# JTAG_CONFIG.net
KiCad netlist of a schematic drawn in Altium Designer
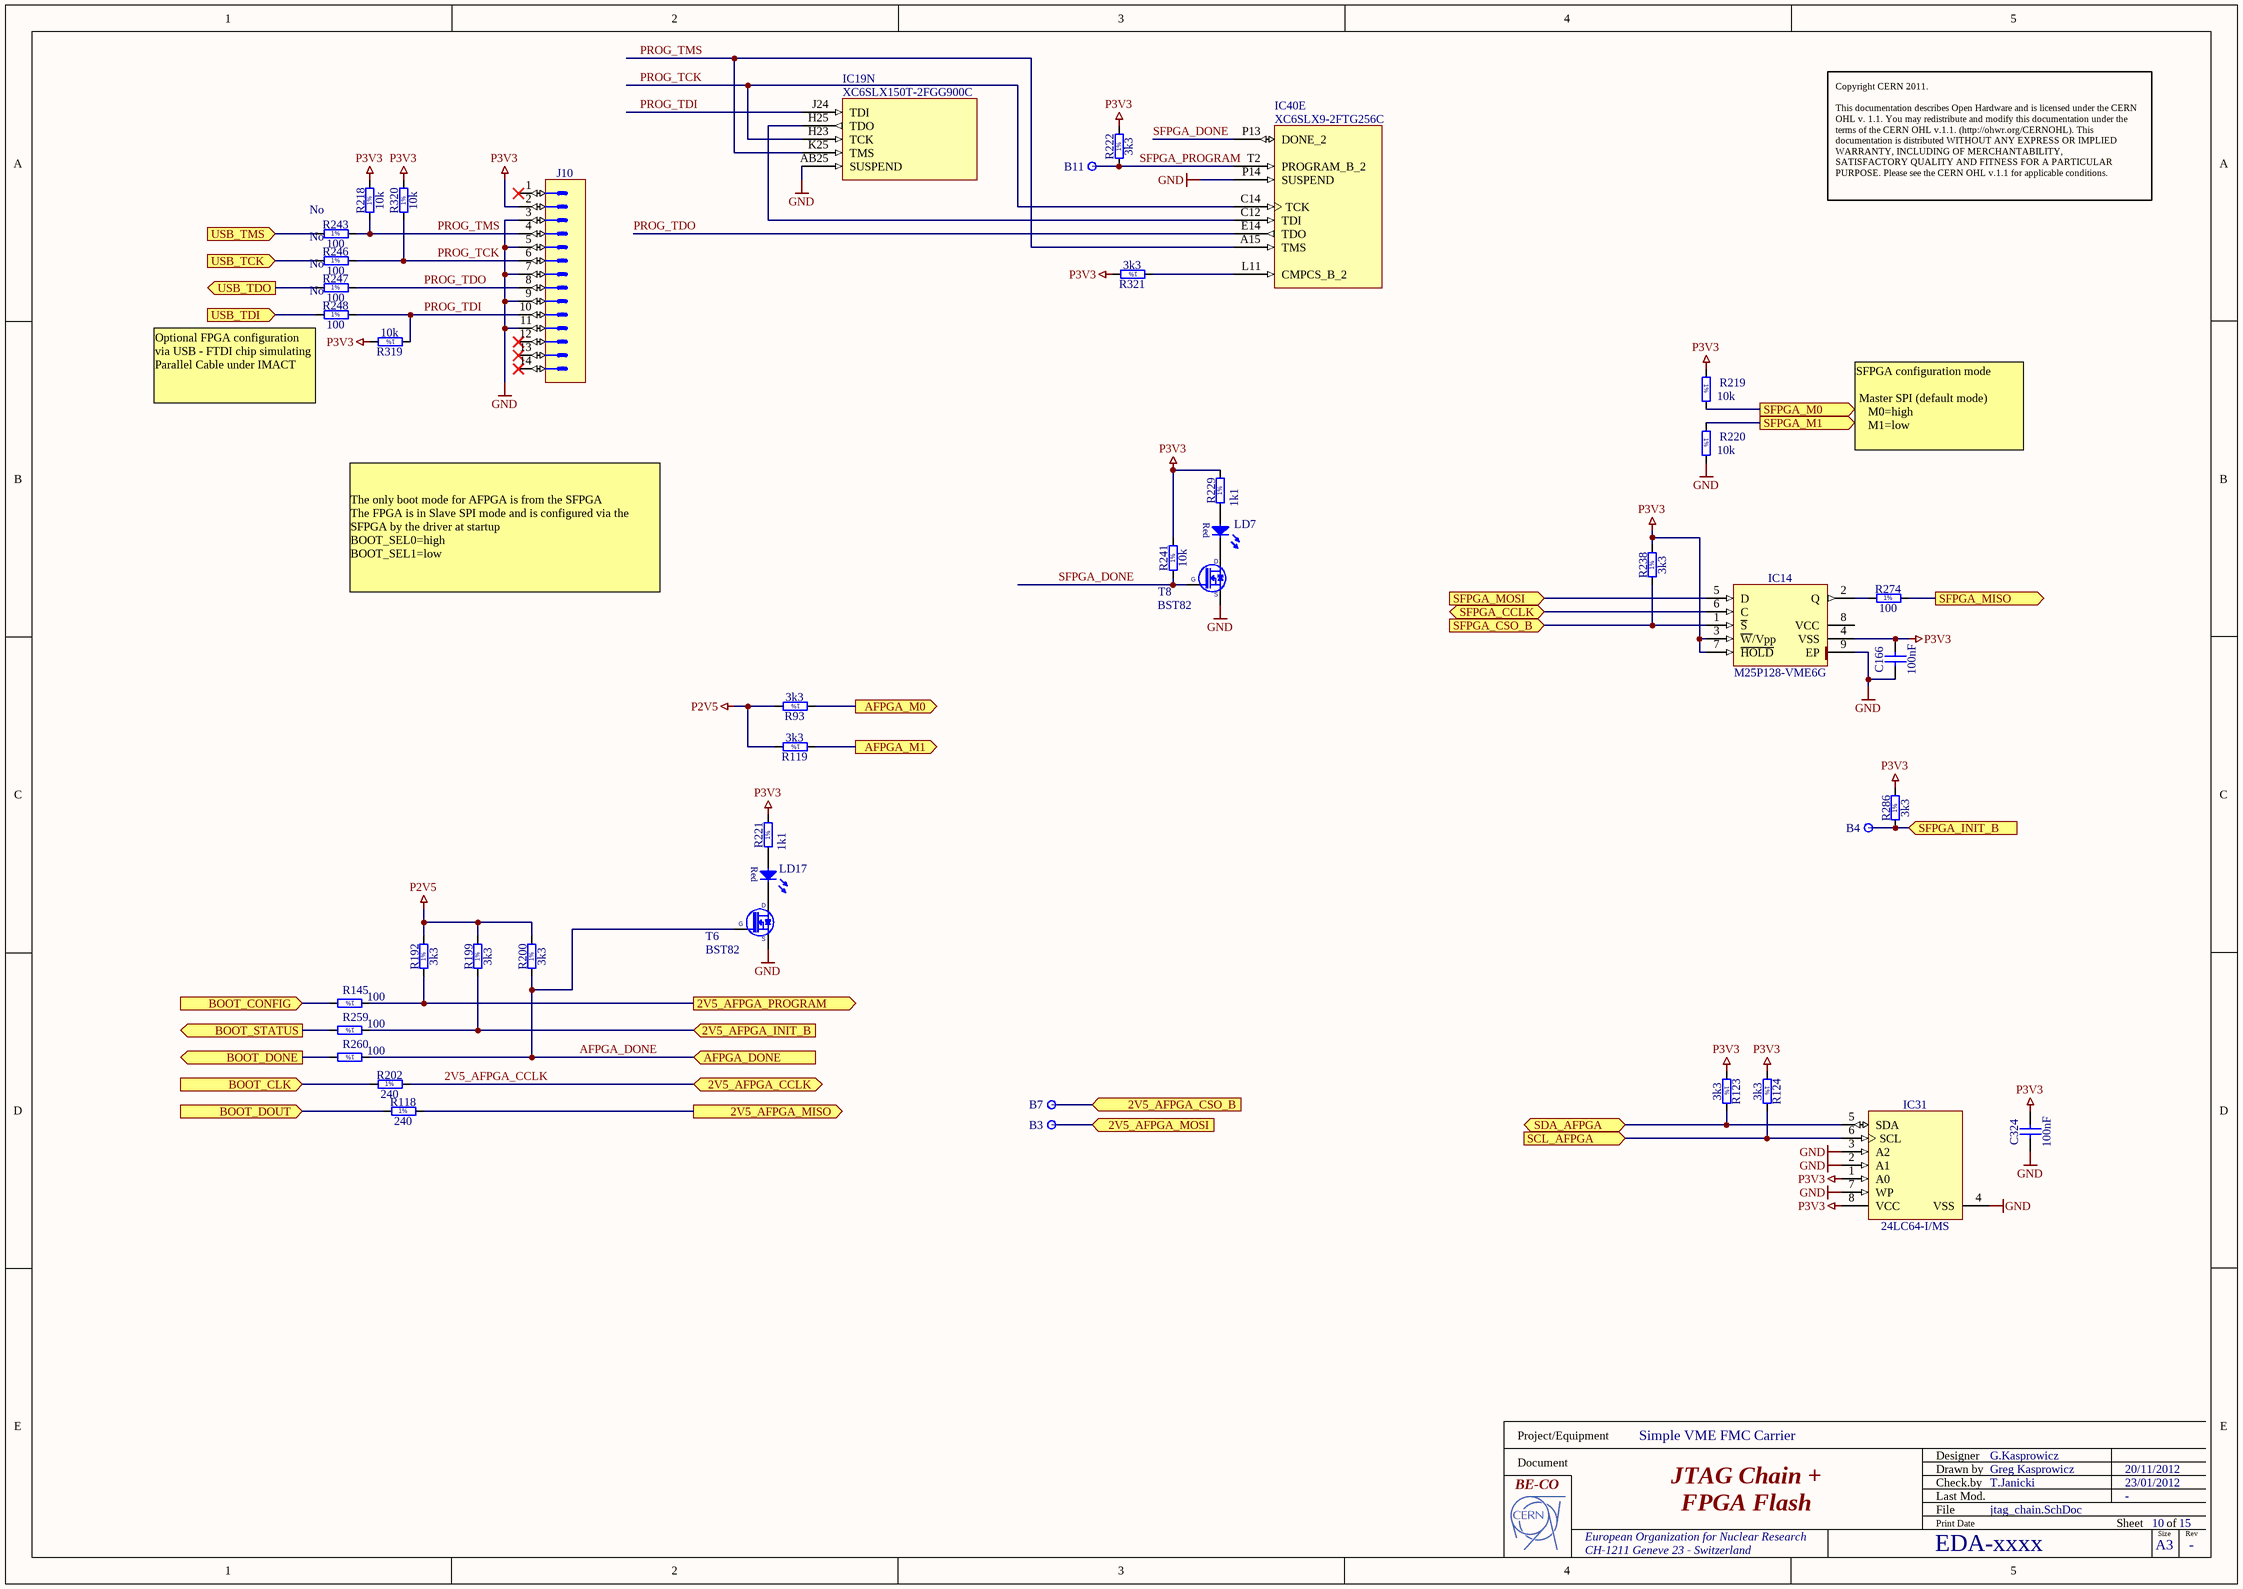
[diagram p0: JTAG&CONFIG.SchDoc]

(export (version "E")
  (design (tool "Eeschema 10.0.6"))
  (components
    (comp (ref "B3")
      (value "Plated Hole")
      (footprint "c130h80")
      (description "Single Terminal Socket")
      (fields (field (name "PART NUMBER") "PLATED_HOLE0.8_PAD1.3") (field (name "AUTHOR") "CERN DEM JLC"))
      (libsource (lib "Eletro-mechanical") (part "Single Terminal Socket"))
    )
    (comp (ref "B4")
      (value "Plated Hole")
      (footprint "c130h80")
      (description "Single Terminal Socket")
      (fields (field (name "PART NUMBER") "PLATED_HOLE0.8_PAD1.3") (field (name "AUTHOR") "CERN DEM JLC"))
      (libsource (lib "Eletro-mechanical") (part "Single Terminal Socket"))
    )
    (comp (ref "B7")
      (value "Plated Hole")
      (footprint "c130h80")
      (description "Single Terminal Socket")
      (fields (field (name "PART NUMBER") "PLATED_HOLE0.8_PAD1.3") (field (name "AUTHOR") "CERN DEM JLC"))
      (libsource (lib "Eletro-mechanical") (part "Single Terminal Socket"))
    )
    (comp (ref "B11")
      (value "Plated Hole")
      (footprint "c130h80")
      (description "Single Terminal Socket")
      (fields (field (name "PART NUMBER") "PLATED_HOLE0.8_PAD1.3") (field (name "AUTHOR") "CERN DEM JLC"))
      (libsource (lib "Eletro-mechanical") (part "Single Terminal Socket"))
    )
    (comp (ref "C166")
      (value "100nF")
      (footprint "CAPC1005X55N")
      (description "Non-polarised capacitor")
      (fields
        (field (name "PART NUMBER") "CC0402_100NF_16V_10%_X7R")
        (field (name "VOLTAGE") "16V")
        (field (name "AUTHOR") "CERN DEM JLC")
      )
      (libsource (lib "Capacitors") (part "Capacitor - non polarized"))
    )
    (comp (ref "C324")
      (value "100nF")
      (footprint "CAPC1005X55N")
      (description "Non-polarised capacitor")
      (fields
        (field (name "PART NUMBER") "CC0402_100NF_16V_10%_X7R")
        (field (name "VOLTAGE") "16V")
        (field (name "AUTHOR") "CERN DEM JLC")
      )
      (libsource (lib "Capacitors") (part "Capacitor - non polarized"))
    )
    (comp (ref "IC14")
      (value "M25P128-VME6G")
      (footprint "PSON127P800X600X100-9N-R640X480")
      (description "128 Mbit (Multilevel), low-voltage, Serial Flash memory with 50-MHz SPI bus interface")
      (fields (field (name "MANUFACTURER") "NUMONYX") (field (name "AUTHOR") "CERN DEM JLC"))
      (libsource (lib "ICs And Semiconductors") (part "M25P128-VME"))
    )
    (comp (ref "IC19")
      (value "XC6SLX150T-2FGG900C")
      (footprint "BGA900C100P30X30_3100X3100X260")
      (description "SPARTAN-6, FPGA, 900-Ball BGA, Commercial Grade, Pb-Free")
      (fields (field (name "MANUFACTURER") "XILINX") (field (name "AUTHOR") "CERN DEM JLC"))
      (libsource (lib "ICs And Semiconductors") (part "XC6SLX150T-2FGG900C"))
    )
    (comp (ref "IC31")
      (value "24LC64-I/MS")
      (footprint "SOP65P490X110-8N")
      (description "64K I2C Serial EEPROM")
      (fields (field (name "MANUFACTURER") "MICROCHIP TECHNOLOGY") (field (name "AUTHOR") "CERN DEM JLC"))
      (libsource (lib "ICs And Semiconductors") (part "24LC64-I/MS"))
    )
    (comp (ref "IC40")
      (value "XC6SLX9-2FTG256C")
      (footprint "BGA256C100P16X16_1700X1700X155")
      (fields (field (name "MANUFACTURER") "XILINX") (field (name "AUTHOR") "CERN DEM JLC"))
      (libsource (lib "ICs And Semiconductors") (part "XC6SLX9-2FTG256C"))
    )
    (comp (ref "J10")
      (value "Milli-Grid")
      (footprint "MOLEX_87832-1420")
      (description "Connector 14 Male")
      (fields
        (field (name "PART NUMBER") "MOLEX_87832-1420")
        (field (name "MANUFACTURER") "MOLEX")
        (field (name "AUTHOR") "CERN DEM JLC")
      )
      (libsource (lib "Connectors") (part "Connector 14 Male"))
    )
    (comp (ref "LD7")
      (value "Red")
      (footprint "LEDC1608X80N_RED")
      (description "LED Red 1C 2A")
      (fields
        (field (name "PART NUMBER") "LED_ROHM_SML-311UTT86K")
        (field (name "MANUFACTURER") "ROHM")
        (field (name "AUTHOR") "CERN DEM JLC")
      )
      (libsource (lib "ICs And Semiconductors") (part "LED Red 1C 2A"))
    )
    (comp (ref "LD17")
      (value "Red")
      (footprint "LEDC1608X80N_RED")
      (description "LED Red 1C 2A")
      (fields
        (field (name "PART NUMBER") "LED_ROHM_SML-311UTT86K")
        (field (name "MANUFACTURER") "ROHM")
        (field (name "AUTHOR") "CERN DEM JLC")
      )
      (libsource (lib "ICs And Semiconductors") (part "LED Red 1C 2A"))
    )
    (comp (ref "R93")
      (value "3k3")
      (footprint "RESC1608X55N")
      (description "Resistor - 1%")
      (fields
        (field (name "PART NUMBER") "R0603_3K3_1%_0.1W_100PPM")
        (field (name "POWER") "0.1W")
        (field (name "AUTHOR") "CERN DEM JLC")
      )
      (libsource (lib "Resistors") (part "Resistor - 1%"))
    )
    (comp (ref "R118")
      (value "240")
      (footprint "RESC1608X55N")
      (description "Resistor - 1%")
      (fields
        (field (name "PART NUMBER") "R0603_240R_1%_0.1W_100PPM")
        (field (name "POWER") "0.1W")
        (field (name "AUTHOR") "CERN DEM JLC")
      )
      (libsource (lib "Resistors") (part "Resistor - 1%"))
    )
    (comp (ref "R119")
      (value "3k3")
      (footprint "RESC1608X55N")
      (description "Resistor - 1%")
      (fields
        (field (name "PART NUMBER") "R0603_3K3_1%_0.1W_100PPM")
        (field (name "POWER") "0.1W")
        (field (name "AUTHOR") "CERN DEM JLC")
      )
      (libsource (lib "Resistors") (part "Resistor - 1%"))
    )
    (comp (ref "R123")
      (value "3k3")
      (footprint "RESC1608X55N")
      (description "Resistor - 1%")
      (fields
        (field (name "PART NUMBER") "R0603_3K3_1%_0.1W_100PPM")
        (field (name "POWER") "0.1W")
        (field (name "AUTHOR") "CERN DEM JLC")
      )
      (libsource (lib "Resistors") (part "Resistor - 1%"))
    )
    (comp (ref "R124")
      (value "3k3")
      (footprint "RESC1608X55N")
      (description "Resistor - 1%")
      (fields
        (field (name "PART NUMBER") "R0603_3K3_1%_0.1W_100PPM")
        (field (name "POWER") "0.1W")
        (field (name "AUTHOR") "CERN DEM JLC")
      )
      (libsource (lib "Resistors") (part "Resistor - 1%"))
    )
    (comp (ref "R145")
      (value "100")
      (footprint "RESC1608X55N")
      (description "Resistor - 1%")
      (fields
        (field (name "PART NUMBER") "R0603_100R_1%_0.1W_100PPM")
        (field (name "POWER") "0.1W")
        (field (name "AUTHOR") "CERN DEM JLC")
      )
      (libsource (lib "Resistors") (part "Resistor - 1%"))
    )
    (comp (ref "R192")
      (value "3k3")
      (footprint "RESC1608X55N")
      (description "Resistor - 1%")
      (fields
        (field (name "PART NUMBER") "R0603_3K3_1%_0.1W_100PPM")
        (field (name "POWER") "0.1W")
        (field (name "AUTHOR") "CERN DEM JLC")
      )
      (libsource (lib "Resistors") (part "Resistor - 1%"))
    )
    (comp (ref "R199")
      (value "3k3")
      (footprint "RESC1608X55N")
      (description "Resistor - 1%")
      (fields
        (field (name "PART NUMBER") "R0603_3K3_1%_0.1W_100PPM")
        (field (name "POWER") "0.1W")
        (field (name "AUTHOR") "CERN DEM JLC")
      )
      (libsource (lib "Resistors") (part "Resistor - 1%"))
    )
    (comp (ref "R200")
      (value "3k3")
      (footprint "RESC1608X55N")
      (description "Resistor - 1%")
      (fields
        (field (name "PART NUMBER") "R0603_3K3_1%_0.1W_100PPM")
        (field (name "POWER") "0.1W")
        (field (name "AUTHOR") "CERN DEM JLC")
      )
      (libsource (lib "Resistors") (part "Resistor - 1%"))
    )
    (comp (ref "R202")
      (value "240")
      (footprint "RESC1608X55N")
      (description "Resistor - 1%")
      (fields
        (field (name "PART NUMBER") "R0603_240R_1%_0.1W_100PPM")
        (field (name "POWER") "0.1W")
        (field (name "AUTHOR") "CERN DEM JLC")
      )
      (libsource (lib "Resistors") (part "Resistor - 1%"))
    )
    (comp (ref "R218")
      (value "10k")
      (footprint "RESC1608X55N")
      (description "Resistor - 1%")
      (fields
        (field (name "PART NUMBER") "R0603_10K_1%_0.1W_100PPM")
        (field (name "POWER") "0.1W")
        (field (name "AUTHOR") "CERN DEM JLC")
      )
      (libsource (lib "Resistors") (part "Resistor - 1%"))
    )
    (comp (ref "R219")
      (value "10k")
      (footprint "RESC1608X55N")
      (description "Resistor - 1%")
      (fields
        (field (name "PART NUMBER") "R0603_10K_1%_0.1W_100PPM")
        (field (name "POWER") "0.1W")
        (field (name "AUTHOR") "CERN DEM JLC")
      )
      (libsource (lib "Resistors") (part "Resistor - 1%"))
    )
    (comp (ref "R220")
      (value "10k")
      (footprint "RESC1608X55N")
      (description "Resistor - 1%")
      (fields
        (field (name "PART NUMBER") "R0603_10K_1%_0.1W_100PPM")
        (field (name "POWER") "0.1W")
        (field (name "AUTHOR") "CERN DEM JLC")
      )
      (libsource (lib "Resistors") (part "Resistor - 1%"))
    )
    (comp (ref "R221")
      (value "1k1")
      (footprint "RESC1608X55N")
      (description "Resistor - 1%")
      (fields
        (field (name "PART NUMBER") "R0603_1K1_1%_0.1W_100PPM")
        (field (name "POWER") "0.1W")
        (field (name "AUTHOR") "CERN DEM JLC")
      )
      (libsource (lib "Resistors") (part "Resistor - 1%"))
    )
    (comp (ref "R222")
      (value "3k3")
      (footprint "RESC1608X55N")
      (description "Resistor - 1%")
      (fields
        (field (name "PART NUMBER") "R0603_3K3_1%_0.1W_100PPM")
        (field (name "POWER") "0.1W")
        (field (name "AUTHOR") "CERN DEM JLC")
      )
      (libsource (lib "Resistors") (part "Resistor - 1%"))
    )
    (comp (ref "R229")
      (value "1k1")
      (footprint "RESC1608X55N")
      (description "Resistor - 1%")
      (fields
        (field (name "PART NUMBER") "R0603_1K1_1%_0.1W_100PPM")
        (field (name "POWER") "0.1W")
        (field (name "AUTHOR") "CERN DEM JLC")
      )
      (libsource (lib "Resistors") (part "Resistor - 1%"))
    )
    (comp (ref "R238")
      (value "3k3")
      (footprint "RESC1608X55N")
      (description "Resistor - 1%")
      (fields
        (field (name "PART NUMBER") "R0603_3K3_1%_0.1W_100PPM")
        (field (name "POWER") "0.1W")
        (field (name "AUTHOR") "CERN DEM JLC")
      )
      (libsource (lib "Resistors") (part "Resistor - 1%"))
    )
    (comp (ref "R241")
      (value "10k")
      (footprint "RESC1608X55N")
      (description "Resistor - 1%")
      (fields
        (field (name "PART NUMBER") "R0603_10K_1%_0.1W_100PPM")
        (field (name "POWER") "0.1W")
        (field (name "AUTHOR") "CERN DEM JLC")
      )
      (libsource (lib "Resistors") (part "Resistor - 1%"))
    )
    (comp (ref "R243")
      (value "100")
      (footprint "RESC1608X55N")
      (description "Resistor - 1%")
      (fields
        (field (name "PART NUMBER") "R0603_100R_1%_0.1W_100PPM")
        (field (name "POWER") "0.1W")
        (field (name "MOUNTED") "No")
        (field (name "AUTHOR") "CERN DEM JLC")
      )
      (libsource (lib "Resistors") (part "Resistor - 1%"))
    )
    (comp (ref "R246")
      (value "100")
      (footprint "RESC1608X55N")
      (description "Resistor - 1%")
      (fields
        (field (name "PART NUMBER") "R0603_100R_1%_0.1W_100PPM")
        (field (name "POWER") "0.1W")
        (field (name "MOUNTED") "No")
        (field (name "AUTHOR") "CERN DEM JLC")
      )
      (libsource (lib "Resistors") (part "Resistor - 1%"))
    )
    (comp (ref "R247")
      (value "100")
      (footprint "RESC1608X55N")
      (description "Resistor - 1%")
      (fields
        (field (name "PART NUMBER") "R0603_100R_1%_0.1W_100PPM")
        (field (name "POWER") "0.1W")
        (field (name "MOUNTED") "No")
        (field (name "AUTHOR") "CERN DEM JLC")
      )
      (libsource (lib "Resistors") (part "Resistor - 1%"))
    )
    (comp (ref "R248")
      (value "100")
      (footprint "RESC1608X55N")
      (description "Resistor - 1%")
      (fields
        (field (name "PART NUMBER") "R0603_100R_1%_0.1W_100PPM")
        (field (name "POWER") "0.1W")
        (field (name "MOUNTED") "No")
        (field (name "AUTHOR") "CERN DEM JLC")
      )
      (libsource (lib "Resistors") (part "Resistor - 1%"))
    )
    (comp (ref "R259")
      (value "100")
      (footprint "RESC1608X55N")
      (description "Resistor - 1%")
      (fields
        (field (name "PART NUMBER") "R0603_100R_1%_0.1W_100PPM")
        (field (name "POWER") "0.1W")
        (field (name "AUTHOR") "CERN DEM JLC")
      )
      (libsource (lib "Resistors") (part "Resistor - 1%"))
    )
    (comp (ref "R260")
      (value "100")
      (footprint "RESC1608X55N")
      (description "Resistor - 1%")
      (fields
        (field (name "PART NUMBER") "R0603_100R_1%_0.1W_100PPM")
        (field (name "POWER") "0.1W")
        (field (name "AUTHOR") "CERN DEM JLC")
      )
      (libsource (lib "Resistors") (part "Resistor - 1%"))
    )
    (comp (ref "R274")
      (value "100")
      (footprint "RESC1608X55N")
      (description "Resistor - 1%")
      (fields
        (field (name "PART NUMBER") "R0603_100R_1%_0.1W_100PPM")
        (field (name "POWER") "0.1W")
        (field (name "AUTHOR") "CERN DEM JLC")
      )
      (libsource (lib "Resistors") (part "Resistor - 1%"))
    )
    (comp (ref "R286")
      (value "3k3")
      (footprint "RESC1608X55N")
      (description "Resistor - 1%")
      (fields
        (field (name "PART NUMBER") "R0603_3K3_1%_0.1W_100PPM")
        (field (name "POWER") "0.1W")
        (field (name "AUTHOR") "CERN DEM JLC")
      )
      (libsource (lib "Resistors") (part "Resistor - 1%"))
    )
    (comp (ref "R319")
      (value "10k")
      (footprint "RESC1608X55N")
      (description "Resistor - 1%")
      (fields
        (field (name "PART NUMBER") "R0603_10K_1%_0.1W_100PPM")
        (field (name "POWER") "0.1W")
        (field (name "AUTHOR") "CERN DEM JLC")
      )
      (libsource (lib "Resistors") (part "Resistor - 1%"))
    )
    (comp (ref "R320")
      (value "10k")
      (footprint "RESC1608X55N")
      (description "Resistor - 1%")
      (fields
        (field (name "PART NUMBER") "R0603_10K_1%_0.1W_100PPM")
        (field (name "POWER") "0.1W")
        (field (name "AUTHOR") "CERN DEM JLC")
      )
      (libsource (lib "Resistors") (part "Resistor - 1%"))
    )
    (comp (ref "R321")
      (value "3k3")
      (footprint "RESC1608X55N")
      (description "Resistor - 1%")
      (fields
        (field (name "PART NUMBER") "R0603_3K3_1%_0.1W_100PPM")
        (field (name "POWER") "0.1W")
        (field (name "AUTHOR") "CERN DEM JLC")
      )
      (libsource (lib "Resistors") (part "Resistor - 1%"))
    )
    (comp (ref "T6")
      (value "BST82")
      (footprint "SOT95P240X110-3N")
      (description "N-CHANNEL MOSFET WITH DIODE")
      (fields (field (name "MANUFACTURER") "NXP SEMICONDUCTORS") (field (name "AUTHOR") "CERN DEM JLC"))
      (libsource (lib "ICs And Semiconductors") (part "N-MOSFET-D 1G 2S 3D"))
    )
    (comp (ref "T8")
      (value "BST82")
      (footprint "SOT95P240X110-3N")
      (description "N-CHANNEL MOSFET WITH DIODE")
      (fields (field (name "MANUFACTURER") "NXP SEMICONDUCTORS") (field (name "AUTHOR") "CERN DEM JLC"))
      (libsource (lib "ICs And Semiconductors") (part "N-MOSFET-D 1G 2S 3D"))
    )
  )
  (nets
    (net (code "1") (name "/2V5_AFPGA_CCLK") (class "Default")
      (node (ref "R202") (pin "2") (pinfunction "2_2") (pintype "passive"))
    )
    (net (code "2") (name "/2V5_AFPGA_CSO_B") (class "Default")
      (node (ref "B7") (pin "1") (pinfunction "1_1") (pintype "bidirectional"))
    )
    (net (code "3") (name "/2V5_AFPGA_INIT_B") (class "Default")
      (node (ref "R199") (pin "1") (pinfunction "1_1") (pintype "passive"))
      (node (ref "R259") (pin "1") (pinfunction "1_1") (pintype "passive"))
    )
    (net (code "4") (name "/2V5_AFPGA_MISO") (class "Default")
      (node (ref "R118") (pin "2") (pinfunction "2_2") (pintype "passive"))
    )
    (net (code "5") (name "/2V5_AFPGA_MOSI") (class "Default")
      (node (ref "B3") (pin "1") (pinfunction "1_1") (pintype "bidirectional"))
    )
    (net (code "6") (name "/2V5_AFPGA_PROGRAM") (class "Default")
      (node (ref "R145") (pin "1") (pinfunction "1_1") (pintype "passive"))
      (node (ref "R192") (pin "1") (pinfunction "1_1") (pintype "passive"))
    )
    (net (code "7") (name "/AFPGA_DONE") (class "Default")
      (node (ref "R200") (pin "1") (pinfunction "1_1") (pintype "passive"))
      (node (ref "R260") (pin "1") (pinfunction "1_1") (pintype "passive"))
      (node (ref "T6") (pin "1") (pinfunction "G_1") (pintype "passive"))
    )
    (net (code "8") (name "/AFPGA_M0") (class "Default")
      (node (ref "R93") (pin "1") (pinfunction "1_1") (pintype "passive"))
    )
    (net (code "9") (name "/AFPGA_M1") (class "Default")
      (node (ref "R119") (pin "1") (pinfunction "1_1") (pintype "passive"))
    )
    (net (code "10") (name "/BOOT_CLK") (class "Default")
      (node (ref "R202") (pin "1") (pinfunction "1_1") (pintype "passive"))
    )
    (net (code "11") (name "/BOOT_CONFIG") (class "Default")
      (node (ref "R145") (pin "2") (pinfunction "2_2") (pintype "passive"))
    )
    (net (code "12") (name "/BOOT_DONE") (class "Default")
      (node (ref "R260") (pin "2") (pinfunction "2_2") (pintype "passive"))
    )
    (net (code "13") (name "/BOOT_DOUT") (class "Default")
      (node (ref "R118") (pin "1") (pinfunction "1_1") (pintype "passive"))
    )
    (net (code "14") (name "/BOOT_STATUS") (class "Default")
      (node (ref "R259") (pin "2") (pinfunction "2_2") (pintype "passive"))
    )
    (net (code "15") (name "/PROG_TCK") (class "Default")
      (node (ref "IC19") (pin "H23") (pinfunction "TCK_H23") (pintype "input"))
      (node (ref "IC40") (pin "C14") (pinfunction "TCK_C14") (pintype "input"))
      (node (ref "J10") (pin "6") (pinfunction "6_6") (pintype "bidirectional"))
      (node (ref "R246") (pin "2") (pinfunction "2_2") (pintype "passive"))
      (node (ref "R320") (pin "1") (pinfunction "1_1") (pintype "passive"))
    )
    (net (code "16") (name "/PROG_TDI") (class "Default")
      (node (ref "IC19") (pin "J24") (pinfunction "TDI_J24") (pintype "input"))
      (node (ref "J10") (pin "10") (pinfunction "10_10") (pintype "bidirectional"))
      (node (ref "R248") (pin "2") (pinfunction "2_2") (pintype "passive"))
      (node (ref "R319") (pin "1") (pinfunction "1_1") (pintype "passive"))
    )
    (net (code "17") (name "/PROG_TDO") (class "Default")
      (node (ref "IC40") (pin "E14") (pinfunction "TDO_E14") (pintype "output"))
      (node (ref "J10") (pin "8") (pinfunction "8_8") (pintype "bidirectional"))
      (node (ref "R247") (pin "2") (pinfunction "2_2") (pintype "passive"))
    )
    (net (code "18") (name "/PROG_TMS") (class "Default")
      (node (ref "IC19") (pin "K25") (pinfunction "TMS_K25") (pintype "input"))
      (node (ref "IC40") (pin "A15") (pinfunction "TMS_A15") (pintype "input"))
      (node (ref "J10") (pin "4") (pinfunction "4_4") (pintype "bidirectional"))
      (node (ref "R218") (pin "1") (pinfunction "1_1") (pintype "passive"))
      (node (ref "R243") (pin "2") (pinfunction "2_2") (pintype "passive"))
    )
    (net (code "19") (name "/SCL_AFPGA") (class "Default")
      (node (ref "IC31") (pin "6") (pinfunction "SCL_6") (pintype "input"))
      (node (ref "R124") (pin "2") (pinfunction "2_2") (pintype "passive"))
    )
    (net (code "20") (name "/SDA_AFPGA") (class "Default")
      (node (ref "IC31") (pin "5") (pinfunction "SDA_5") (pintype "bidirectional"))
      (node (ref "R123") (pin "2") (pinfunction "2_2") (pintype "passive"))
    )
    (net (code "21") (name "/SFPGA_CCLK") (class "Default")
      (node (ref "IC14") (pin "6") (pinfunction "C_6") (pintype "input"))
    )
    (net (code "22") (name "/SFPGA_CSO_B") (class "Default")
      (node (ref "IC14") (pin "1") (pinfunction "~{S}_1") (pintype "input"))
      (node (ref "R238") (pin "1") (pinfunction "1_1") (pintype "passive"))
    )
    (net (code "23") (name "/SFPGA_DONE") (class "Default")
      (node (ref "IC40") (pin "P13") (pinfunction "DONE_2_P13") (pintype "bidirectional"))
      (node (ref "R241") (pin "1") (pinfunction "1_1") (pintype "passive"))
      (node (ref "T8") (pin "1") (pinfunction "G_1") (pintype "passive"))
    )
    (net (code "24") (name "/SFPGA_INIT_B") (class "Default")
      (node (ref "B4") (pin "1") (pinfunction "1_1") (pintype "bidirectional"))
      (node (ref "R286") (pin "1") (pinfunction "1_1") (pintype "passive"))
    )
    (net (code "25") (name "/SFPGA_M0") (class "Default")
      (node (ref "R219") (pin "2") (pinfunction "2_2") (pintype "passive"))
    )
    (net (code "26") (name "/SFPGA_M1") (class "Default")
      (node (ref "R220") (pin "1") (pinfunction "1_1") (pintype "passive"))
    )
    (net (code "27") (name "/SFPGA_MISO") (class "Default")
      (node (ref "R274") (pin "2") (pinfunction "2_2") (pintype "passive"))
    )
    (net (code "28") (name "/SFPGA_MOSI") (class "Default")
      (node (ref "IC14") (pin "5") (pinfunction "D_5") (pintype "input"))
    )
    (net (code "29") (name "/SFPGA_PROGRAM") (class "Default")
      (node (ref "B11") (pin "1") (pinfunction "1_1") (pintype "bidirectional"))
      (node (ref "IC40") (pin "T2") (pinfunction "PROGRAM_B_2_T2") (pintype "input"))
      (node (ref "R222") (pin "1") (pinfunction "1_1") (pintype "passive"))
    )
    (net (code "30") (name "/USB_TCK") (class "Default")
      (node (ref "R246") (pin "1") (pinfunction "1_1") (pintype "passive"))
    )
    (net (code "31") (name "/USB_TDI") (class "Default")
      (node (ref "R248") (pin "1") (pinfunction "1_1") (pintype "passive"))
    )
    (net (code "32") (name "/USB_TDO") (class "Default")
      (node (ref "R247") (pin "1") (pinfunction "1_1") (pintype "passive"))
    )
    (net (code "33") (name "/USB_TMS") (class "Default")
      (node (ref "R243") (pin "1") (pinfunction "1_1") (pintype "passive"))
    )
    (net (code "34") (name "GND") (class "Default")
      (node (ref "C166") (pin "2") (pinfunction "2_2") (pintype "passive"))
      (node (ref "C324") (pin "2") (pinfunction "2_2") (pintype "passive"))
      (node (ref "IC14") (pin "9") (pinfunction "EP_9") (pintype "power_in"))
      (node (ref "IC19") (pin "AB25") (pinfunction "SUSPEND_AB25") (pintype "input"))
      (node (ref "IC31") (pin "2") (pinfunction "A1_2") (pintype "input"))
      (node (ref "IC31") (pin "3") (pinfunction "A2_3") (pintype "input"))
      (node (ref "IC31") (pin "4") (pinfunction "VSS_4") (pintype "power_in"))
      (node (ref "IC31") (pin "7") (pinfunction "WP_7") (pintype "input"))
      (node (ref "IC40") (pin "P14") (pinfunction "SUSPEND_P14") (pintype "input"))
      (node (ref "J10") (pin "11") (pinfunction "11_11") (pintype "bidirectional"))
      (node (ref "J10") (pin "3") (pinfunction "3_3") (pintype "bidirectional"))
      (node (ref "J10") (pin "5") (pinfunction "5_5") (pintype "bidirectional"))
      (node (ref "J10") (pin "7") (pinfunction "7_7") (pintype "bidirectional"))
      (node (ref "J10") (pin "9") (pinfunction "9_9") (pintype "bidirectional"))
      (node (ref "R220") (pin "2") (pinfunction "2_2") (pintype "passive"))
      (node (ref "T6") (pin "2") (pinfunction "S_2") (pintype "passive"))
      (node (ref "T8") (pin "2") (pinfunction "S_2") (pintype "passive"))
    )
    (net (code "35") (name "Net-(IC14-Q)") (class "Default")
      (node (ref "IC14") (pin "2") (pinfunction "Q_2") (pintype "output"))
      (node (ref "R274") (pin "1") (pinfunction "1_1") (pintype "passive"))
    )
    (net (code "36") (name "Net-(IC19N-TDO)") (class "Default")
      (node (ref "IC19") (pin "H25") (pinfunction "TDO_H25") (pintype "output"))
      (node (ref "IC40") (pin "C12") (pinfunction "TDI_C12") (pintype "input"))
    )
    (net (code "37") (name "Net-(IC40E-CMPCS_B_2)") (class "Default")
      (node (ref "IC40") (pin "L11") (pinfunction "CMPCS_B_2_L11") (pintype "input"))
      (node (ref "R321") (pin "1") (pinfunction "1_1") (pintype "passive"))
    )
    (net (code "38") (name "Net-(LD7-A)") (class "Default")
      (node (ref "LD7") (pin "2") (pinfunction "A_2") (pintype "passive"))
      (node (ref "R229") (pin "1") (pinfunction "1_1") (pintype "passive"))
    )
    (net (code "39") (name "Net-(LD7-C)") (class "Default")
      (node (ref "LD7") (pin "1") (pinfunction "C_1") (pintype "passive"))
      (node (ref "T8") (pin "3") (pinfunction "D_3") (pintype "passive"))
    )
    (net (code "40") (name "Net-(LD17-A)") (class "Default")
      (node (ref "LD17") (pin "2") (pinfunction "A_2") (pintype "passive"))
      (node (ref "R221") (pin "1") (pinfunction "1_1") (pintype "passive"))
    )
    (net (code "41") (name "Net-(LD17-C)") (class "Default")
      (node (ref "LD17") (pin "1") (pinfunction "C_1") (pintype "passive"))
      (node (ref "T6") (pin "3") (pinfunction "D_3") (pintype "passive"))
    )
    (net (code "42") (name "P2V5") (class "Default")
      (node (ref "R119") (pin "2") (pinfunction "2_2") (pintype "passive"))
      (node (ref "R192") (pin "2") (pinfunction "2_2") (pintype "passive"))
      (node (ref "R199") (pin "2") (pinfunction "2_2") (pintype "passive"))
      (node (ref "R200") (pin "2") (pinfunction "2_2") (pintype "passive"))
      (node (ref "R93") (pin "2") (pinfunction "2_2") (pintype "passive"))
    )
    (net (code "43") (name "P3V3") (class "Default")
      (node (ref "C166") (pin "1") (pinfunction "1_1") (pintype "passive"))
      (node (ref "C324") (pin "1") (pinfunction "1_1") (pintype "passive"))
      (node (ref "IC14") (pin "3") (pinfunction "~{W}/Vpp_3") (pintype "input"))
      (node (ref "IC14") (pin "4") (pinfunction "VSS_4") (pintype "power_in"))
      (node (ref "IC14") (pin "7") (pinfunction "~{HOLD}_7") (pintype "input"))
      (node (ref "IC31") (pin "1") (pinfunction "A0_1") (pintype "input"))
      (node (ref "IC31") (pin "8") (pinfunction "VCC_8") (pintype "power_in"))
      (node (ref "J10") (pin "2") (pinfunction "2_2") (pintype "bidirectional"))
      (node (ref "R123") (pin "1") (pinfunction "1_1") (pintype "passive"))
      (node (ref "R124") (pin "1") (pinfunction "1_1") (pintype "passive"))
      (node (ref "R218") (pin "2") (pinfunction "2_2") (pintype "passive"))
      (node (ref "R219") (pin "1") (pinfunction "1_1") (pintype "passive"))
      (node (ref "R221") (pin "2") (pinfunction "2_2") (pintype "passive"))
      (node (ref "R222") (pin "2") (pinfunction "2_2") (pintype "passive"))
      (node (ref "R229") (pin "2") (pinfunction "2_2") (pintype "passive"))
      (node (ref "R238") (pin "2") (pinfunction "2_2") (pintype "passive"))
      (node (ref "R241") (pin "2") (pinfunction "2_2") (pintype "passive"))
      (node (ref "R286") (pin "2") (pinfunction "2_2") (pintype "passive"))
      (node (ref "R319") (pin "2") (pinfunction "2_2") (pintype "passive"))
      (node (ref "R320") (pin "2") (pinfunction "2_2") (pintype "passive"))
      (node (ref "R321") (pin "2") (pinfunction "2_2") (pintype "passive"))
    )
    (net (code "44") (name "unconnected-(IC14-VCC-Pad8)") (class "Default")
      (node (ref "IC14") (pin "8") (pinfunction "VCC_8") (pintype "power_in"))
    )
    (net (code "45") (name "unconnected-(J10-Pad1)") (class "Default")
      (node (ref "J10") (pin "1") (pinfunction "1_1") (pintype "bidirectional+no_connect"))
    )
    (net (code "46") (name "unconnected-(J10-Pad12)") (class "Default")
      (node (ref "J10") (pin "12") (pinfunction "12_12") (pintype "bidirectional+no_connect"))
    )
    (net (code "47") (name "unconnected-(J10-Pad13)") (class "Default")
      (node (ref "J10") (pin "13") (pinfunction "13_13") (pintype "bidirectional+no_connect"))
    )
    (net (code "48") (name "unconnected-(J10-Pad14)") (class "Default")
      (node (ref "J10") (pin "14") (pinfunction "14_14") (pintype "bidirectional+no_connect"))
    )
  )
)
